# ProPrj_Final_Main_2026-01-12.net
KiCad netlist of a schematic drawn in EasyEDA Pro
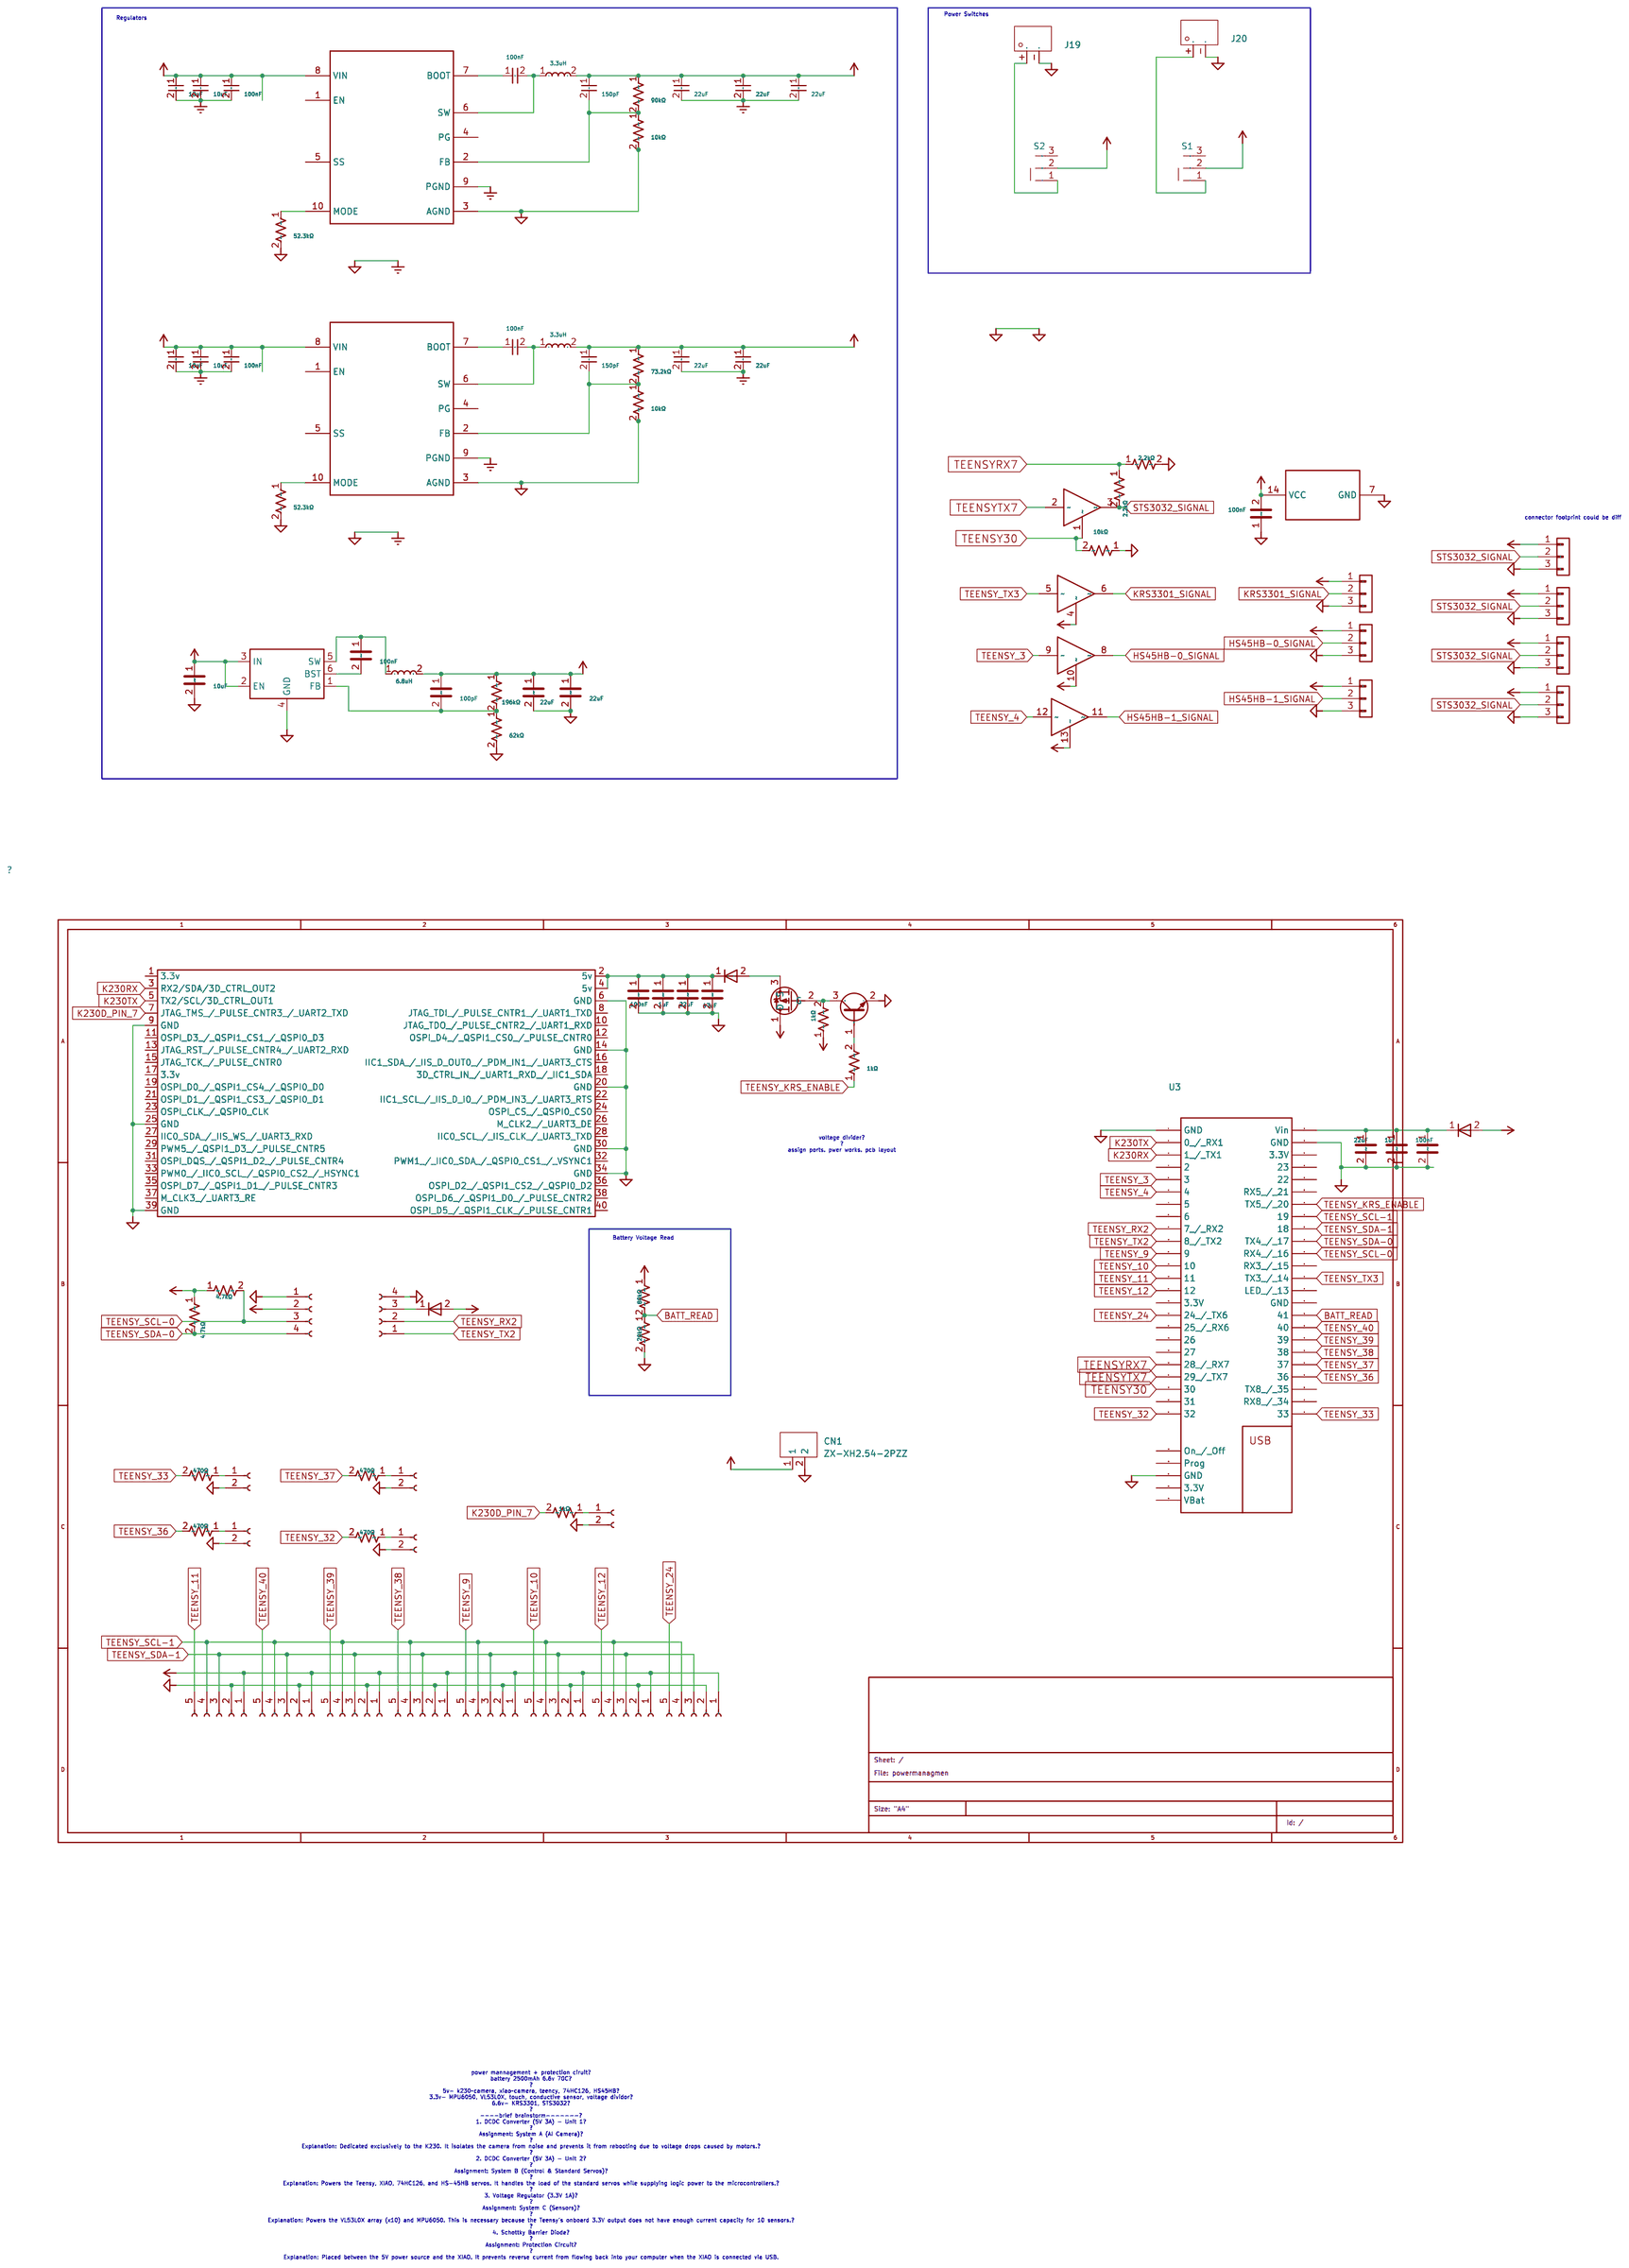
[diagram p0: schematic sheet]

(export (version "E")
  (design (tool "Eeschema 10.0.6"))
  (components
    (comp (ref "C1")
      (value "100nF")
      (description "Capacitance:100nF Tolerance:±10% Tolerance:±10% Voltage Rating:50V Temperature Coefficient:X7R")
      (fields
        (field (name "Manufacturer Part") "TCC0603X7R104K500CT")
        (field (name "Manufacturer") "CCTC(三环)")
      )
      (libsource (lib "easyedapro") (part "Device_C"))
    )
    (comp (ref "C2")
      (value "22uF")
      (description "Capacitance:22uF Tolerance:±20% Tolerance:±20% Voltage Rating:10V Temperature Coefficient:X5R")
      (fields
        (field (name "Manufacturer Part") "CL10A226MP8NUNE")
        (field (name "Manufacturer") "SAMSUNG(三星)")
      )
      (libsource (lib "easyedapro") (part "Device_C"))
    )
    (comp (ref "C3")
      (value "1uF")
      (description "Capacitance:1uF Tolerance:±10% Tolerance:±10% Voltage Rating:50V Temperature Coefficient:X5R")
      (fields
        (field (name "Manufacturer Part") "CL10A105KB8NNNC")
        (field (name "Manufacturer") "SAMSUNG(三星)")
      )
      (libsource (lib "easyedapro") (part "Device_C"))
    )
    (comp (ref "C4")
      (value "100nF")
      (description "Capacitance:100nF Tolerance:±10% Tolerance:±10% Voltage Rating:50V Temperature Coefficient:X7R")
      (fields
        (field (name "Manufacturer Part") "TCC0603X7R104K500CT")
        (field (name "Manufacturer") "CCTC(三环)")
      )
      (libsource (lib "easyedapro") (part "Device_C"))
    )
    (comp (ref "C5")
      (value "10uF")
      (description "Capacitance:10uF Tolerance:±20% Tolerance:±20% Voltage Rating:16V Temperature Coefficient:X5R")
      (fields
        (field (name "Manufacturer Part") "CL10A106MO8NQNC")
        (field (name "Manufacturer") "SAMSUNG(三星)")
      )
      (libsource (lib "easyedapro") (part "Device_C_Small"))
    )
    (comp (ref "C6")
      (value "22uF")
      (description "Capacitance:22uF Tolerance:±20% Tolerance:±20% Voltage Rating:10V Temperature Coefficient:X5R")
      (fields
        (field (name "Manufacturer Part") "CL10A226MP8NUNE")
        (field (name "Manufacturer") "SAMSUNG(三星)")
      )
      (libsource (lib "easyedapro") (part "Device_C_Small"))
    )
    (comp (ref "C7")
      (value "22uF")
      (description "Capacitance:22uF Tolerance:±20% Tolerance:±20% Voltage Rating:10V Temperature Coefficient:X5R")
      (fields
        (field (name "Manufacturer Part") "CL10A226MP8NUNE")
        (field (name "Manufacturer") "SAMSUNG(三星)")
      )
      (libsource (lib "easyedapro") (part "Device_C_Small"))
    )
    (comp (ref "C8")
      (value "22uF")
      (description "Capacitance:22uF Tolerance:±20% Tolerance:±20% Voltage Rating:10V Temperature Coefficient:X5R")
      (fields
        (field (name "Manufacturer Part") "CL10A226MP8NUNE")
        (field (name "Manufacturer") "SAMSUNG(三星)")
      )
      (libsource (lib "easyedapro") (part "Device_C_Small"))
    )
    (comp (ref "C10")
      (value "100pF")
      (description "Capacitance:100pF Tolerance:±5% Tolerance:±5% Voltage Rating:50V Temperature Coefficient:C0G")
      (fields
        (field (name "Manufacturer Part") "CL10C101JB8NNNC")
        (field (name "Manufacturer") "SAMSUNG(三星)")
      )
      (libsource (lib "easyedapro") (part "Device_C"))
    )
    (comp (ref "C12")
      (value "150pF")
      (description "Capacitance:150pF Tolerance:±10% Tolerance:±10% Voltage Rating:50V Temperature Coefficient:X7R")
      (fields (field (name "Manufacturer Part") "0603B151K500NT") (field (name "Manufacturer") "FH(风华)"))
      (libsource (lib "easyedapro") (part "Device_C_Small"))
    )
    (comp (ref "C17")
      (value "100nF")
      (description "Capacitance:100nF Tolerance:±10% Tolerance:±10% Voltage Rating:50V Temperature Coefficient:X7R")
      (fields
        (field (name "Manufacturer Part") "TCC0603X7R104K500CT")
        (field (name "Manufacturer") "CCTC(三环)")
      )
      (libsource (lib "easyedapro") (part "Device_C"))
    )
    (comp (ref "C18")
      (value "1uF")
      (description "Capacitance:1uF Tolerance:±10% Tolerance:±10% Voltage Rating:50V Temperature Coefficient:X5R")
      (fields
        (field (name "Manufacturer Part") "CL10A105KB8NNNC")
        (field (name "Manufacturer") "SAMSUNG(三星)")
      )
      (libsource (lib "easyedapro") (part "Device_C"))
    )
    (comp (ref "C19")
      (value "22uF")
      (description "Capacitance:22uF Tolerance:±20% Tolerance:±20% Voltage Rating:10V Temperature Coefficient:X5R")
      (fields
        (field (name "Manufacturer Part") "CL10A226MP8NUNE")
        (field (name "Manufacturer") "SAMSUNG(三星)")
      )
      (libsource (lib "easyedapro") (part "Device_C"))
    )
    (comp (ref "C20")
      (value "47uF")
      (description "Capacitance:47uF Tolerance:±20% Tolerance:±20% Voltage Rating:6.3V Temperature Coefficient:X5R")
      (fields
        (field (name "Manufacturer Part") "GRM188R60J476ME15D")
        (field (name "Manufacturer") "muRata(村田)")
      )
      (libsource (lib "easyedapro") (part "Device_C"))
    )
    (comp (ref "C21")
      (value "22uF")
      (description "Capacitance:22uF Tolerance:±20% Tolerance:±20% Voltage Rating:10V Temperature Coefficient:X5R")
      (fields
        (field (name "Manufacturer Part") "CL10A226MP8NUNE")
        (field (name "Manufacturer") "SAMSUNG(三星)")
      )
      (libsource (lib "easyedapro") (part "Device_C"))
    )
    (comp (ref "C22")
      (value "10uF")
      (description "Capacitance:10uF Tolerance:±20% Tolerance:±20% Voltage Rating:16V Temperature Coefficient:X5R")
      (fields
        (field (name "Manufacturer Part") "CL10A106MO8NQNC")
        (field (name "Manufacturer") "SAMSUNG(三星)")
      )
      (libsource (lib "easyedapro") (part "Device_C_Small"))
    )
    (comp (ref "C23")
      (value "100nF")
      (description "Capacitance:100nF Tolerance:±10% Tolerance:±10% Voltage Rating:50V Temperature Coefficient:X7R")
      (fields
        (field (name "Manufacturer Part") "TCC0603X7R104K500CT")
        (field (name "Manufacturer") "CCTC(三环)")
      )
      (libsource (lib "easyedapro") (part "Device_C"))
    )
    (comp (ref "C24")
      (value "100nF")
      (description "Capacitance:100nF Tolerance:±10% Tolerance:±10% Voltage Rating:50V Temperature Coefficient:X7R")
      (fields
        (field (name "Manufacturer Part") "TCC0603X7R104K500CT")
        (field (name "Manufacturer") "CCTC(三环)")
      )
      (libsource (lib "easyedapro") (part "Device_C_Small"))
    )
    (comp (ref "C28")
      (value "100nF")
      (description "Capacitance:100nF Tolerance:±10% Tolerance:±10% Voltage Rating:50V Temperature Coefficient:X7R")
      (fields
        (field (name "Manufacturer Part") "TCC0603X7R104K500CT")
        (field (name "Manufacturer") "CCTC(三环)")
      )
      (libsource (lib "easyedapro") (part "Device_C_Small"))
    )
    (comp (ref "C29")
      (value "22uF")
      (description "Capacitance:22uF Tolerance:±20% Tolerance:±20% Voltage Rating:10V Temperature Coefficient:X5R")
      (fields
        (field (name "Manufacturer Part") "CL10A226MP8NUNE")
        (field (name "Manufacturer") "SAMSUNG(三星)")
      )
      (libsource (lib "easyedapro") (part "Device_C"))
    )
    (comp (ref "C31")
      (value "10uF")
      (description "Capacitance:10uF Tolerance:±20% Tolerance:±20% Voltage Rating:16V Temperature Coefficient:X5R")
      (fields
        (field (name "Manufacturer Part") "CL10A106MO8NQNC")
        (field (name "Manufacturer") "SAMSUNG(三星)")
      )
      (libsource (lib "easyedapro") (part "Device_C"))
    )
    (comp (ref "C32")
      (value "100nF")
      (description "Capacitance:100nF Tolerance:±10% Tolerance:±10% Voltage Rating:50V Temperature Coefficient:X7R")
      (fields
        (field (name "Manufacturer Part") "TCC0603X7R104K500CT")
        (field (name "Manufacturer") "CCTC(三环)")
      )
      (libsource (lib "easyedapro") (part "Device_C_Small"))
    )
    (comp (ref "C33")
      (value "100nF")
      (description "Capacitance:100nF Tolerance:±10% Tolerance:±10% Voltage Rating:50V Temperature Coefficient:X7R")
      (fields
        (field (name "Manufacturer Part") "TCC0603X7R104K500CT")
        (field (name "Manufacturer") "CCTC(三环)")
      )
      (libsource (lib "easyedapro") (part "Device_C_Small"))
    )
    (comp (ref "C34")
      (value "10uF")
      (description "Capacitance:10uF Tolerance:±20% Tolerance:±20% Voltage Rating:16V Temperature Coefficient:X5R")
      (fields
        (field (name "Manufacturer Part") "CL10A106MO8NQNC")
        (field (name "Manufacturer") "SAMSUNG(三星)")
      )
      (libsource (lib "easyedapro") (part "Device_C_Small"))
    )
    (comp (ref "C35")
      (value "10uF")
      (description "Capacitance:10uF Tolerance:±20% Tolerance:±20% Voltage Rating:16V Temperature Coefficient:X5R")
      (fields
        (field (name "Manufacturer Part") "CL10A106MO8NQNC")
        (field (name "Manufacturer") "SAMSUNG(三星)")
      )
      (libsource (lib "easyedapro") (part "Device_C_Small"))
    )
    (comp (ref "C36")
      (value "22uF")
      (description "Capacitance:22uF Tolerance:±20% Tolerance:±20% Voltage Rating:10V Temperature Coefficient:X5R")
      (fields
        (field (name "Manufacturer Part") "CL10A226MP8NUNE")
        (field (name "Manufacturer") "SAMSUNG(三星)")
      )
      (libsource (lib "easyedapro") (part "Device_C_Small"))
    )
    (comp (ref "C37")
      (value "22uF")
      (description "Capacitance:22uF Tolerance:±20% Tolerance:±20% Voltage Rating:10V Temperature Coefficient:X5R")
      (fields
        (field (name "Manufacturer Part") "CL10A226MP8NUNE")
        (field (name "Manufacturer") "SAMSUNG(三星)")
      )
      (libsource (lib "easyedapro") (part "Device_C_Small"))
    )
    (comp (ref "C39")
      (value "150pF")
      (description "Capacitance:150pF Tolerance:±10% Tolerance:±10% Voltage Rating:50V Temperature Coefficient:X7R")
      (fields (field (name "Manufacturer Part") "0603B151K500NT") (field (name "Manufacturer") "FH(风华)"))
      (libsource (lib "easyedapro") (part "Device_C_Small"))
    )
    (comp (ref "CN1")
      (value "ZX-XH2.54-2PZZ")
      (footprint "easyedapro:CONN-TH_2P-P2.50_HX25003-2A")
      (fields (field (name "Manufacturer") "Megastar(兆星)"))
      (libsource (lib "easyedapro") (part "ZX-XH2.54-2PZZ"))
    )
    (comp (ref "D1")
      (value "BAT60B")
      (fields (field (name "Manufacturer") "R+O(宏嘉诚)"))
      (libsource (lib "easyedapro") (part "Diode_1N4148WT"))
    )
    (comp (ref "D2")
      (value "BAT60B")
      (fields (field (name "Manufacturer") "R+O(宏嘉诚)"))
      (libsource (lib "easyedapro") (part "Diode_1N4148WT"))
    )
    (comp (ref "D3")
      (value "BAT60B")
      (fields (field (name "Manufacturer") "R+O(宏嘉诚)"))
      (libsource (lib "easyedapro") (part "Diode_1N4148WT"))
    )
    (comp (ref "J1")
      (value "B3B-XH-A(LF)(SN)")
      (fields (field (name "Manufacturer") "JST"))
      (libsource (lib "easyedapro") (part "Connector_Generic_Conn_01x03"))
    )
    (comp (ref "J2")
      (value "PZ254V-11-03P")
      (fields (field (name "Manufacturer") "XFCN(兴飞)"))
      (libsource (lib "easyedapro") (part "Connector_Generic_Conn_01x03"))
    )
    (comp (ref "J3")
      (value "PZ254V-11-03P")
      (fields (field (name "Manufacturer") "XFCN(兴飞)"))
      (libsource (lib "easyedapro") (part "Connector_Generic_Conn_01x03"))
    )
    (comp (ref "J4")
      (value "PZ254V-11-03P")
      (fields (field (name "Manufacturer") "XFCN(兴飞)"))
      (libsource (lib "easyedapro") (part "Connector_Generic_Conn_01x03"))
    )
    (comp (ref "J5")
      (value "B4B-PH-K-S(LF)(SN)")
      (fields (field (name "Manufacturer") "JST"))
      (libsource (lib "easyedapro") (part "Connector_Conn_01x04_Socket"))
    )
    (comp (ref "J6")
      (value "B2B-XH-A(LF)(SN)")
      (fields (field (name "Manufacturer") "JST"))
      (libsource (lib "easyedapro") (part "Connector_Conn_01x02_Socket"))
    )
    (comp (ref "J7")
      (value "B2B-XH-A(LF)(SN)")
      (fields (field (name "Manufacturer") "JST"))
      (libsource (lib "easyedapro") (part "Connector_Conn_01x02_Socket"))
    )
    (comp (ref "J8")
      (value "B2B-XH-A(LF)(SN)")
      (fields (field (name "Manufacturer") "JST"))
      (libsource (lib "easyedapro") (part "Connector_Conn_01x02_Socket"))
    )
    (comp (ref "J9")
      (value "B2B-XH-A(LF)(SN)")
      (fields (field (name "Manufacturer") "JST"))
      (libsource (lib "easyedapro") (part "Connector_Conn_01x02_Socket"))
    )
    (comp (ref "J10")
      (value "B2B-XH-A(LF)(SN)")
      (fields (field (name "Manufacturer") "JST"))
      (libsource (lib "easyedapro") (part "Connector_Conn_01x02_Socket"))
    )
    (comp (ref "J12")
      (value "B3B-XH-A(LF)(SN)")
      (fields (field (name "Manufacturer") "JST"))
      (libsource (lib "easyedapro") (part "Connector_Generic_Conn_01x03"))
    )
    (comp (ref "J13")
      (value "B3B-XH-A(LF)(SN)")
      (fields (field (name "Manufacturer") "JST"))
      (libsource (lib "easyedapro") (part "Connector_Generic_Conn_01x03"))
    )
    (comp (ref "J14")
      (value "B3B-XH-A(LF)(SN)")
      (fields (field (name "Manufacturer") "JST"))
      (libsource (lib "easyedapro") (part "Connector_Generic_Conn_01x03"))
    )
    (comp (ref "J18")
      (value "B5B-PH-K-S(LF)(SN)")
      (fields (field (name "Manufacturer") "JST"))
      (libsource (lib "easyedapro") (part "Connector_Conn_01x05_Socket"))
    )
    (comp (ref "J19")
      (value "XT60-F")
      (footprint "easyedapro:CONN-TH_XT60PB-F")
      (fields (field (name "Manufacturer") "AMASS(艾迈斯)"))
      (libsource (lib "easyedapro") (part "XT60-F"))
    )
    (comp (ref "J20")
      (value "XT60-F")
      (footprint "easyedapro:CONN-TH_XT60PB-F")
      (fields (field (name "Manufacturer") "AMASS(艾迈斯)"))
      (libsource (lib "easyedapro") (part "XT60-F"))
    )
    (comp (ref "J25")
      (value "B5B-PH-K-S(LF)(SN)")
      (fields (field (name "Manufacturer") "JST"))
      (libsource (lib "easyedapro") (part "Connector_Conn_01x05_Socket"))
    )
    (comp (ref "J26")
      (value "B5B-PH-K-S(LF)(SN)")
      (fields (field (name "Manufacturer") "JST"))
      (libsource (lib "easyedapro") (part "Connector_Conn_01x05_Socket"))
    )
    (comp (ref "J27")
      (value "B5B-PH-K-S(LF)(SN)")
      (fields (field (name "Manufacturer") "JST"))
      (libsource (lib "easyedapro") (part "Connector_Conn_01x05_Socket"))
    )
    (comp (ref "J28")
      (value "B5B-PH-K-S(LF)(SN)")
      (fields (field (name "Manufacturer") "JST"))
      (libsource (lib "easyedapro") (part "Connector_Conn_01x05_Socket"))
    )
    (comp (ref "J29")
      (value "B5B-PH-K-S(LF)(SN)")
      (fields (field (name "Manufacturer") "JST"))
      (libsource (lib "easyedapro") (part "Connector_Conn_01x05_Socket"))
    )
    (comp (ref "J31")
      (value "22035045")
      (fields (field (name "Manufacturer") "MOLEX"))
      (libsource (lib "easyedapro") (part "Connector_Conn_01x04_Socket"))
    )
    (comp (ref "J32")
      (value "B5B-PH-K-S(LF)(SN)")
      (fields (field (name "Manufacturer") "JST"))
      (libsource (lib "easyedapro") (part "Connector_Conn_01x05_Socket"))
    )
    (comp (ref "J33")
      (value "B5B-PH-K-S(LF)(SN)")
      (fields (field (name "Manufacturer") "JST"))
      (libsource (lib "easyedapro") (part "Connector_Conn_01x05_Socket"))
    )
    (comp (ref "L1")
      (value "3.3uH")
      (description "Inductance: Tolerance:±20% Tolerance:±20% Current Rating: DC Resistance(DCR):19.9mΩ")
      (fields (field (name "Manufacturer Part") "CYA0650-3.3UH") (field (name "Manufacturer") "SHOU HAN(首韩)"))
      (libsource (lib "easyedapro") (part "Device_L"))
    )
    (comp (ref "L3")
      (value "6.8uH")
      (fields
        (field (name "Manufacturer Part") "MGFL2012F6R8MT-LF")
        (field (name "Manufacturer") "microgate(麦捷科技)")
      )
      (libsource (lib "easyedapro") (part "Device_L"))
    )
    (comp (ref "L4")
      (value "3.3uH")
      (description "Inductance: Tolerance:±20% Tolerance:±20% Current Rating: DC Resistance(DCR):19.9mΩ")
      (fields (field (name "Manufacturer Part") "CYA0650-3.3UH") (field (name "Manufacturer") "SHOU HAN(首韩)"))
      (libsource (lib "easyedapro") (part "Device_L"))
    )
    (comp (ref "Q1")
      (value "AO3401A")
      (fields (field (name "Manufacturer") "UMW(友台半导体)"))
      (libsource (lib "easyedapro") (part "Simulation_SPICE_PMOS"))
    )
    (comp (ref "Q2")
      (value "SS8050(RANGE:200-350)")
      (fields (field (name "Manufacturer") "CJ(江苏长电/长晶)"))
      (libsource (lib "easyedapro") (part "Transistor_BJT_SS8050"))
    )
    (comp (ref "R1")
      (value "10kΩ")
      (fields
        (field (name "Manufacturer Part") "0603WAF1002T5E")
        (field (name "Manufacturer") "UNI-ROYAL(厚声)")
      )
      (libsource (lib "easyedapro") (part "Device_R_US"))
    )
    (comp (ref "R2")
      (value "4.7kΩ")
      (fields (field (name "Manufacturer Part") "FRC0603F4701TS") (field (name "Manufacturer") "FOJAN(富捷)"))
      (libsource (lib "easyedapro") (part "Device_R_US"))
    )
    (comp (ref "R3")
      (value "4.7kΩ")
      (fields (field (name "Manufacturer Part") "FRC0603F4701TS") (field (name "Manufacturer") "FOJAN(富捷)"))
      (libsource (lib "easyedapro") (part "Device_R_US"))
    )
    (comp (ref "R4")
      (value "470Ω")
      (fields
        (field (name "Manufacturer Part") "0603WAF4700T5E")
        (field (name "Manufacturer") "UNI-ROYAL(厚声)")
      )
      (libsource (lib "easyedapro") (part "Device_R_US"))
    )
    (comp (ref "R5")
      (value "470Ω")
      (fields
        (field (name "Manufacturer Part") "0603WAF4700T5E")
        (field (name "Manufacturer") "UNI-ROYAL(厚声)")
      )
      (libsource (lib "easyedapro") (part "Device_R_US"))
    )
    (comp (ref "R6")
      (value "470Ω")
      (fields
        (field (name "Manufacturer Part") "0603WAF4700T5E")
        (field (name "Manufacturer") "UNI-ROYAL(厚声)")
      )
      (libsource (lib "easyedapro") (part "Device_R_US"))
    )
    (comp (ref "R7")
      (value "470Ω")
      (fields
        (field (name "Manufacturer Part") "0603WAF4700T5E")
        (field (name "Manufacturer") "UNI-ROYAL(厚声)")
      )
      (libsource (lib "easyedapro") (part "Device_R_US"))
    )
    (comp (ref "R8")
      (value "1kΩ")
      (fields
        (field (name "Manufacturer Part") "0603WAF1001T5E")
        (field (name "Manufacturer") "UNI-ROYAL(厚声)")
      )
      (libsource (lib "easyedapro") (part "Device_R_US"))
    )
    (comp (ref "R9")
      (value "2.2kΩ")
      (fields
        (field (name "Manufacturer Part") "0603WAF2201T5E")
        (field (name "Manufacturer") "UNI-ROYAL(厚声)")
      )
      (libsource (lib "easyedapro") (part "Device_R_US"))
    )
    (comp (ref "R10")
      (value "2.2kΩ")
      (fields
        (field (name "Manufacturer Part") "0603WAF2201T5E")
        (field (name "Manufacturer") "UNI-ROYAL(厚声)")
      )
      (libsource (lib "easyedapro") (part "Device_R_US"))
    )
    (comp (ref "R11")
      (value "52.3kΩ")
      (fields (field (name "Manufacturer Part") "FRC0603F5232TS") (field (name "Manufacturer") "FOJAN(富捷)"))
      (libsource (lib "easyedapro") (part "Device_R_US"))
    )
    (comp (ref "R12")
      (value "196kΩ")
      (fields (field (name "Manufacturer Part") "FRC0603F1963TS") (field (name "Manufacturer") "FOJAN(富捷)"))
      (libsource (lib "easyedapro") (part "Device_R_US"))
    )
    (comp (ref "R13")
      (value "1kΩ")
      (fields
        (field (name "Manufacturer Part") "0603WAF1001T5E")
        (field (name "Manufacturer") "UNI-ROYAL(厚声)")
      )
      (libsource (lib "easyedapro") (part "Device_R_US"))
    )
    (comp (ref "R14")
      (value "1kΩ")
      (fields
        (field (name "Manufacturer Part") "0603WAF1001T5E")
        (field (name "Manufacturer") "UNI-ROYAL(厚声)")
      )
      (libsource (lib "easyedapro") (part "Device_R_US"))
    )
    (comp (ref "R15")
      (value "62kΩ")
      (fields (field (name "Manufacturer Part") "FRC0603F6202TS") (field (name "Manufacturer") "FOJAN(富捷)"))
      (libsource (lib "easyedapro") (part "Device_R_US"))
    )
    (comp (ref "R20")
      (value "90kΩ")
      (fields (field (name "Manufacturer Part") "RT1206DRE0790KL") (field (name "Manufacturer") "YAGEO(国巨)"))
      (libsource (lib "easyedapro") (part "Device_R_US"))
    )
    (comp (ref "R21")
      (value "10kΩ")
      (fields
        (field (name "Manufacturer Part") "0603WAF1002T5E")
        (field (name "Manufacturer") "UNI-ROYAL(厚声)")
      )
      (libsource (lib "easyedapro") (part "Device_R_US"))
    )
    (comp (ref "R22")
      (value "80kΩ")
      (fields (field (name "Manufacturer Part") "ARG03FTC8002N") (field (name "Manufacturer") "Viking(光颉)"))
      (libsource (lib "easyedapro") (part "Device_R_US"))
    )
    (comp (ref "R23")
      (value "20kΩ")
      (fields (field (name "Manufacturer Part") "FRC0603F2002TS") (field (name "Manufacturer") "FOJAN(富捷)"))
      (libsource (lib "easyedapro") (part "Device_R_US"))
    )
    (comp (ref "R24")
      (value "52.3kΩ")
      (fields (field (name "Manufacturer Part") "FRC0603F5232TS") (field (name "Manufacturer") "FOJAN(富捷)"))
      (libsource (lib "easyedapro") (part "Device_R_US"))
    )
    (comp (ref "R25")
      (value "73.2kΩ")
      (fields (field (name "Manufacturer Part") "FRC0603F7322TS") (field (name "Manufacturer") "FOJAN(富捷)"))
      (libsource (lib "easyedapro") (part "Device_R_US"))
    )
    (comp (ref "R26")
      (value "10kΩ")
      (fields
        (field (name "Manufacturer Part") "0603WAF1002T5E")
        (field (name "Manufacturer") "UNI-ROYAL(厚声)")
      )
      (libsource (lib "easyedapro") (part "Device_R_US"))
    )
    (comp (ref "S1")
      (value "SS-12M11G4")
      (footprint "easyedapro:SW-TH_XKB_SS-12M11XX")
      (fields (field (name "Manufacturer") "XKB Connection(中国星坤)"))
      (libsource (lib "easyedapro") (part "SS-12M11G4"))
    )
    (comp (ref "S2")
      (value "SS-12M11G4")
      (footprint "easyedapro:SW-TH_XKB_SS-12M11XX")
      (fields (field (name "Manufacturer") "XKB Connection(中国星坤)"))
      (libsource (lib "easyedapro") (part "SS-12M11G4"))
    )
    (comp (ref "U1")
      (value "DM74LS126AM")
      (fields (field (name "Manufacturer") "onsemi(安森美)"))
      (libsource (lib "easyedapro") (part "74xx_74LS126"))
    )
    (comp (ref "U2")
      (value "FH-00148")
      (fields (field (name "Manufacturer") "Liansheng(连盛)"))
      (libsource (lib "easyedapro") (part "K230D_K230D-Zero"))
    )
    (comp (ref "U3") (value "TEENSY 4.1") (libsource (lib "easyedapro") (part "TEENSY 4.1")))
    (comp (ref "U4")
      (value "AP63201WU-7")
      (fields (field (name "Manufacturer") "DIODES(美台)"))
      (libsource (lib "easyedapro") (part "Regulator_Switching_AP63201WU"))
    )
    (comp (ref "U5")
      (value "TPS56A37RPAR")
      (fields (field (name "Manufacturer") "TI(德州仪器)"))
      (libsource (lib "easyedapro") (part "2026-01-05_00-17-44_TPS56A37RPAR"))
    )
    (comp (ref "U6")
      (value "TPS56A37RPAR")
      (fields (field (name "Manufacturer") "TI(德州仪器)"))
      (libsource (lib "easyedapro") (part "2026-01-05_00-17-44_TPS56A37RPAR"))
    )
  )
  (nets
    (net (code "1") (name "+3.3V") (class "Default")
      (node (ref "C10") (pin "1") (pinfunction "~_1") (pintype "unspecified"))
      (node (ref "C21") (pin "1") (pinfunction "~_1") (pintype "unspecified"))
      (node (ref "C29") (pin "1") (pinfunction "~_1") (pintype "unspecified"))
      (node (ref "J18") (pin "1") (pinfunction "Pin_1_1") (pintype "unspecified"))
      (node (ref "J25") (pin "1") (pinfunction "Pin_1_1") (pintype "unspecified"))
      (node (ref "J26") (pin "1") (pinfunction "Pin_1_1") (pintype "unspecified"))
      (node (ref "J27") (pin "1") (pinfunction "Pin_1_1") (pintype "unspecified"))
      (node (ref "J28") (pin "1") (pinfunction "Pin_1_1") (pintype "unspecified"))
      (node (ref "J29") (pin "1") (pinfunction "Pin_1_1") (pintype "unspecified"))
      (node (ref "J32") (pin "1") (pinfunction "Pin_1_1") (pintype "unspecified"))
      (node (ref "J33") (pin "1") (pinfunction "Pin_1_1") (pintype "unspecified"))
      (node (ref "J5") (pin "2") (pinfunction "Pin_2_2") (pintype "unspecified"))
      (node (ref "L3") (pin "2") (pinfunction "2_2") (pintype "unspecified"))
      (node (ref "R12") (pin "1") (pinfunction "~_1") (pintype "unspecified"))
      (node (ref "R2") (pin "1") (pinfunction "~_1") (pintype "unspecified"))
      (node (ref "R3") (pin "1") (pinfunction "~_1") (pintype "unspecified"))
    )
    (net (code "2") (name "+5V") (class "Default")
      (node (ref "C1") (pin "2") (pinfunction "~_2") (pintype "unspecified"))
      (node (ref "C36") (pin "1") (pinfunction "~_1") (pintype "unspecified"))
      (node (ref "C37") (pin "1") (pinfunction "~_1") (pintype "unspecified"))
      (node (ref "C39") (pin "1") (pinfunction "~_1") (pintype "unspecified"))
      (node (ref "D1") (pin "2") (pinfunction "A_2") (pintype "unspecified"))
      (node (ref "D3") (pin "2") (pinfunction "A_2") (pintype "unspecified"))
      (node (ref "L4") (pin "2") (pinfunction "2_2") (pintype "unspecified"))
      (node (ref "Q1") (pin "1") (pinfunction "D_1") (pintype "unspecified"))
      (node (ref "R13") (pin "1") (pinfunction "~_1") (pintype "unspecified"))
      (node (ref "R25") (pin "1") (pinfunction "~_1") (pintype "unspecified"))
      (node (ref "U1") (pin "10") (pinfunction "~_10") (pintype "input"))
      (node (ref "U1") (pin "13") (pinfunction "~_13") (pintype "input"))
      (node (ref "U1") (pin "14") (pinfunction "VCC_14") (pintype "unspecified"))
      (node (ref "U1") (pin "4") (pinfunction "~_4") (pintype "input"))
    )
    (net (code "3") (name "+6V") (class "Default")
      (node (ref "C12") (pin "1") (pinfunction "~_1") (pintype "unspecified"))
      (node (ref "C6") (pin "1") (pinfunction "~_1") (pintype "unspecified"))
      (node (ref "C7") (pin "1") (pinfunction "~_1") (pintype "unspecified"))
      (node (ref "C8") (pin "1") (pinfunction "~_1") (pintype "unspecified"))
      (node (ref "J1") (pin "1") (pinfunction "Pin_1_1") (pintype "unspecified"))
      (node (ref "J12") (pin "1") (pinfunction "Pin_1_1") (pintype "unspecified"))
      (node (ref "J13") (pin "1") (pinfunction "Pin_1_1") (pintype "unspecified"))
      (node (ref "J14") (pin "1") (pinfunction "Pin_1_1") (pintype "unspecified"))
      (node (ref "J3") (pin "1") (pinfunction "Pin_1_1") (pintype "unspecified"))
      (node (ref "J4") (pin "1") (pinfunction "Pin_1_1") (pintype "unspecified"))
      (node (ref "L1") (pin "2") (pinfunction "2_2") (pintype "unspecified"))
      (node (ref "R20") (pin "1") (pinfunction "~_1") (pintype "unspecified"))
    )
    (net (code "4") (name "+BATT") (class "Default")
      (node (ref "C22") (pin "1") (pinfunction "~_1") (pintype "unspecified"))
      (node (ref "C24") (pin "1") (pinfunction "~_1") (pintype "unspecified"))
      (node (ref "C31") (pin "1") (pinfunction "~_1") (pintype "unspecified"))
      (node (ref "C33") (pin "1") (pinfunction "~_1") (pintype "unspecified"))
      (node (ref "C34") (pin "1") (pinfunction "~_1") (pintype "unspecified"))
      (node (ref "C35") (pin "1") (pinfunction "~_1") (pintype "unspecified"))
      (node (ref "C5") (pin "1") (pinfunction "~_1") (pintype "unspecified"))
      (node (ref "CN1") (pin "1") (pinfunction "1_1") (pintype "unspecified"))
      (node (ref "J2") (pin "1") (pinfunction "Pin_1_1") (pintype "unspecified"))
      (node (ref "R22") (pin "1") (pinfunction "~_1") (pintype "unspecified"))
      (node (ref "S1") (pin "2") (pinfunction "2_2") (pintype "unspecified"))
      (node (ref "S2") (pin "2") (pinfunction "2_2") (pintype "unspecified"))
      (node (ref "U4") (pin "2") (pinfunction "EN_2") (pintype "input"))
      (node (ref "U4") (pin "3") (pinfunction "IN_3") (pintype "unspecified"))
      (node (ref "U5") (pin "8") (pinfunction "VIN_8") (pintype "unspecified"))
      (node (ref "U6") (pin "8") (pinfunction "VIN_8") (pintype "unspecified"))
    )
    (net (code "5") (name "AGND") (class "Default")
      (node (ref "R24") (pin "2") (pinfunction "~_2") (pintype "unspecified"))
      (node (ref "R26") (pin "2") (pinfunction "~_2") (pintype "unspecified"))
      (node (ref "U6") (pin "3") (pinfunction "AGND_3") (pintype "unspecified"))
    )
    (net (code "6") (name "AGND1") (class "Default")
      (node (ref "R11") (pin "2") (pinfunction "~_2") (pintype "unspecified"))
      (node (ref "R21") (pin "2") (pinfunction "~_2") (pintype "unspecified"))
      (node (ref "U5") (pin "3") (pinfunction "AGND_3") (pintype "unspecified"))
    )
    (net (code "7") (name "BATT_READ") (class "Default")
      (node (ref "R22") (pin "2") (pinfunction "~_2") (pintype "unspecified"))
      (node (ref "R23") (pin "1") (pinfunction "~_1") (pintype "unspecified"))
      (node (ref "U3") (pin "40") (pinfunction "41_40") (pintype "unspecified"))
    )
    (net (code "8") (name "HS45HB-0_SIGNAL") (class "Default")
      (node (ref "J3") (pin "2") (pinfunction "Pin_2_2") (pintype "unspecified"))
      (node (ref "U1") (pin "8") (pinfunction "~_8") (pintype "unspecified"))
    )
    (net (code "9") (name "HS45HB-1_SIGNAL") (class "Default")
      (node (ref "J4") (pin "2") (pinfunction "Pin_2_2") (pintype "unspecified"))
      (node (ref "U1") (pin "11") (pinfunction "~_11") (pintype "unspecified"))
    )
    (net (code "10") (name "K230D_PIN_7") (class "Default")
      (node (ref "R8") (pin "2") (pinfunction "~_2") (pintype "unspecified"))
      (node (ref "U2") (pin "7") (pinfunction "JTAG_TMS_/_PULSE_CNTR3_/_UART2_TXD_7") (pintype "output"))
    )
    (net (code "11") (name "K230RX") (class "Default")
      (node (ref "U2") (pin "3") (pinfunction "RX2/SDA/3D_CTRL_OUT2_3") (pintype "input"))
      (node (ref "U3") (pin "3") (pinfunction "1_/_TX1_3") (pintype "unspecified"))
    )
    (net (code "12") (name "K230TX") (class "Default")
      (node (ref "U2") (pin "5") (pinfunction "TX2/SCL/3D_CTRL_OUT1_5") (pintype "bidirectional"))
      (node (ref "U3") (pin "2") (pinfunction "0_/_RX1_2") (pintype "unspecified"))
    )
    (net (code "13") (name "KRS3301_SIGNAL") (class "Default")
      (node (ref "J2") (pin "2") (pinfunction "Pin_2_2") (pintype "unspecified"))
      (node (ref "U1") (pin "6") (pinfunction "~_6") (pintype "unspecified"))
    )
    (net (code "14") (name "MGND") (class "Default")
      (node (ref "C22") (pin "2") (pinfunction "~_2") (pintype "unspecified"))
      (node (ref "C24") (pin "2") (pinfunction "~_2") (pintype "unspecified"))
      (node (ref "C5") (pin "2") (pinfunction "~_2") (pintype "unspecified"))
      (node (ref "C6") (pin "2") (pinfunction "~_2") (pintype "unspecified"))
      (node (ref "C7") (pin "2") (pinfunction "~_2") (pintype "unspecified"))
      (node (ref "C8") (pin "2") (pinfunction "~_2") (pintype "unspecified"))
      (node (ref "J19") (pin "-") (pinfunction "2_-") (pintype "input"))
      (node (ref "U5") (pin "9") (pinfunction "PGND_9") (pintype "unspecified"))
    )
    (net (code "15") (name "Net-(D1-K)") (class "Default")
      (node (ref "C2") (pin "1") (pinfunction "~_1") (pintype "unspecified"))
      (node (ref "C3") (pin "1") (pinfunction "~_1") (pintype "unspecified"))
      (node (ref "C4") (pin "1") (pinfunction "~_1") (pintype "unspecified"))
      (node (ref "D1") (pin "1") (pinfunction "K_1") (pintype "unspecified"))
      (node (ref "U3") (pin "25") (pinfunction "Vin_25") (pintype "unspecified"))
    )
    (net (code "16") (name "Net-(D2-A)") (class "Default")
      (node (ref "D2") (pin "2") (pinfunction "A_2") (pintype "unspecified"))
      (node (ref "Q1") (pin "3") (pinfunction "S_3") (pintype "unspecified"))
    )
    (net (code "17") (name "Net-(D2-K)") (class "Default")
      (node (ref "C17") (pin "1") (pinfunction "~_1") (pintype "unspecified"))
      (node (ref "C18") (pin "1") (pinfunction "~_1") (pintype "unspecified"))
      (node (ref "C19") (pin "1") (pinfunction "~_1") (pintype "unspecified"))
      (node (ref "C20") (pin "1") (pinfunction "~_1") (pintype "unspecified"))
      (node (ref "D2") (pin "1") (pinfunction "K_1") (pintype "unspecified"))
      (node (ref "U2") (pin "2") (pinfunction "5v_2") (pintype "unspecified"))
      (node (ref "U2") (pin "4") (pinfunction "5v_4") (pintype "bidirectional"))
    )
    (net (code "18") (name "Net-(D3-K)") (class "Default")
      (node (ref "D3") (pin "1") (pinfunction "K_1") (pintype "unspecified"))
      (node (ref "J31") (pin "3") (pinfunction "Pin_3_3") (pintype "unspecified"))
    )
    (net (code "19") (name "Net-(J6-Pin_1)") (class "Default")
      (node (ref "J6") (pin "1") (pinfunction "Pin_1_1") (pintype "unspecified"))
      (node (ref "R4") (pin "1") (pinfunction "~_1") (pintype "unspecified"))
    )
    (net (code "20") (name "Net-(J7-Pin_1)") (class "Default")
      (node (ref "J7") (pin "1") (pinfunction "Pin_1_1") (pintype "unspecified"))
      (node (ref "R5") (pin "1") (pinfunction "~_1") (pintype "unspecified"))
    )
    (net (code "21") (name "Net-(J8-Pin_1)") (class "Default")
      (node (ref "J8") (pin "1") (pinfunction "Pin_1_1") (pintype "unspecified"))
      (node (ref "R6") (pin "1") (pinfunction "~_1") (pintype "unspecified"))
    )
    (net (code "22") (name "Net-(J9-Pin_1)") (class "Default")
      (node (ref "J9") (pin "1") (pinfunction "Pin_1_1") (pintype "unspecified"))
      (node (ref "R7") (pin "1") (pinfunction "~_1") (pintype "unspecified"))
    )
    (net (code "23") (name "Net-(J10-Pin_1)") (class "Default")
      (node (ref "J10") (pin "1") (pinfunction "Pin_1_1") (pintype "unspecified"))
      (node (ref "R8") (pin "1") (pinfunction "~_1") (pintype "unspecified"))
    )
    (net (code "24") (name "Net-(J19-1)") (class "Default")
      (node (ref "J19") (pin "+") (pinfunction "1_+") (pintype "input"))
      (node (ref "S2") (pin "1") (pinfunction "1_1") (pintype "unspecified"))
    )
    (net (code "25") (name "Net-(J20-1)") (class "Default")
      (node (ref "J20") (pin "+") (pinfunction "1_+") (pintype "input"))
      (node (ref "S1") (pin "1") (pinfunction "1_1") (pintype "unspecified"))
    )
    (net (code "26") (name "Net-(Q1-G)") (class "Default")
      (node (ref "Q1") (pin "2") (pinfunction "G_2") (pintype "input"))
      (node (ref "Q2") (pin "3") (pinfunction "C_3") (pintype "unspecified"))
      (node (ref "R13") (pin "2") (pinfunction "~_2") (pintype "unspecified"))
    )
    (net (code "27") (name "Net-(Q2-B)") (class "Default")
      (node (ref "Q2") (pin "1") (pinfunction "B_1") (pintype "input"))
      (node (ref "R14") (pin "2") (pinfunction "~_2") (pintype "unspecified"))
    )
    (net (code "28") (name "Net-(U4-BST)") (class "Default")
      (node (ref "C23") (pin "2") (pinfunction "~_2") (pintype "unspecified"))
      (node (ref "U4") (pin "6") (pinfunction "BST_6") (pintype "unspecified"))
    )
    (net (code "29") (name "Net-(U4-FB)") (class "Default")
      (node (ref "C10") (pin "2") (pinfunction "~_2") (pintype "unspecified"))
      (node (ref "R12") (pin "2") (pinfunction "~_2") (pintype "unspecified"))
      (node (ref "R15") (pin "1") (pinfunction "~_1") (pintype "unspecified"))
      (node (ref "U4") (pin "1") (pinfunction "FB_1") (pintype "input"))
    )
    (net (code "30") (name "Net-(U4-SW)") (class "Default")
      (node (ref "C23") (pin "1") (pinfunction "~_1") (pintype "unspecified"))
      (node (ref "L3") (pin "1") (pinfunction "1_1") (pintype "unspecified"))
      (node (ref "U4") (pin "5") (pinfunction "SW_5") (pintype "output"))
    )
    (net (code "31") (name "Net-(U5-BOOT)") (class "Default")
      (node (ref "C28") (pin "1") (pinfunction "~_1") (pintype "unspecified"))
      (node (ref "U5") (pin "7") (pinfunction "BOOT_7") (pintype "unspecified"))
    )
    (net (code "32") (name "Net-(U5-FB)") (class "Default")
      (node (ref "C12") (pin "2") (pinfunction "~_2") (pintype "unspecified"))
      (node (ref "R20") (pin "2") (pinfunction "~_2") (pintype "unspecified"))
      (node (ref "R21") (pin "1") (pinfunction "~_1") (pintype "unspecified"))
      (node (ref "U5") (pin "2") (pinfunction "FB_2") (pintype "unspecified"))
    )
    (net (code "33") (name "Net-(U5-MODE)") (class "Default")
      (node (ref "R11") (pin "1") (pinfunction "~_1") (pintype "unspecified"))
      (node (ref "U5") (pin "10") (pinfunction "MODE_10") (pintype "unspecified"))
    )
    (net (code "34") (name "Net-(U5-SW)") (class "Default")
      (node (ref "C28") (pin "2") (pinfunction "~_2") (pintype "unspecified"))
      (node (ref "L1") (pin "1") (pinfunction "1_1") (pintype "unspecified"))
      (node (ref "U5") (pin "6") (pinfunction "SW_6") (pintype "unspecified"))
    )
    (net (code "35") (name "Net-(U6-BOOT)") (class "Default")
      (node (ref "C32") (pin "1") (pinfunction "~_1") (pintype "unspecified"))
      (node (ref "U6") (pin "7") (pinfunction "BOOT_7") (pintype "unspecified"))
    )
    (net (code "36") (name "Net-(U6-FB)") (class "Default")
      (node (ref "C39") (pin "2") (pinfunction "~_2") (pintype "unspecified"))
      (node (ref "R25") (pin "2") (pinfunction "~_2") (pintype "unspecified"))
      (node (ref "R26") (pin "1") (pinfunction "~_1") (pintype "unspecified"))
      (node (ref "U6") (pin "2") (pinfunction "FB_2") (pintype "unspecified"))
    )
    (net (code "37") (name "Net-(U6-MODE)") (class "Default")
      (node (ref "R24") (pin "1") (pinfunction "~_1") (pintype "unspecified"))
      (node (ref "U6") (pin "10") (pinfunction "MODE_10") (pintype "unspecified"))
    )
    (net (code "38") (name "Net-(U6-SW)") (class "Default")
      (node (ref "C32") (pin "2") (pinfunction "~_2") (pintype "unspecified"))
      (node (ref "L4") (pin "1") (pinfunction "1_1") (pintype "unspecified"))
      (node (ref "U6") (pin "6") (pinfunction "SW_6") (pintype "unspecified"))
    )
    (net (code "39") (name "POWER_GND") (class "Default")
      (node (ref "C1") (pin "1") (pinfunction "~_1") (pintype "unspecified"))
      (node (ref "C17") (pin "2") (pinfunction "~_2") (pintype "unspecified"))
      (node (ref "C18") (pin "2") (pinfunction "~_2") (pintype "unspecified"))
      (node (ref "C19") (pin "2") (pinfunction "~_2") (pintype "unspecified"))
      (node (ref "C2") (pin "2") (pinfunction "~_2") (pintype "unspecified"))
      (node (ref "C20") (pin "2") (pinfunction "~_2") (pintype "unspecified"))
      (node (ref "C21") (pin "2") (pinfunction "~_2") (pintype "unspecified"))
      (node (ref "C29") (pin "2") (pinfunction "~_2") (pintype "unspecified"))
      (node (ref "C3") (pin "2") (pinfunction "~_2") (pintype "unspecified"))
      (node (ref "C31") (pin "2") (pinfunction "~_2") (pintype "unspecified"))
      (node (ref "C33") (pin "2") (pinfunction "~_2") (pintype "unspecified"))
      (node (ref "C34") (pin "2") (pinfunction "~_2") (pintype "unspecified"))
      (node (ref "C35") (pin "2") (pinfunction "~_2") (pintype "unspecified"))
      (node (ref "C36") (pin "2") (pinfunction "~_2") (pintype "unspecified"))
      (node (ref "C37") (pin "2") (pinfunction "~_2") (pintype "unspecified"))
      (node (ref "C4") (pin "2") (pinfunction "~_2") (pintype "unspecified"))
      (node (ref "CN1") (pin "2") (pinfunction "2_2") (pintype "unspecified"))
      (node (ref "J1") (pin "3") (pinfunction "Pin_3_3") (pintype "unspecified"))
      (node (ref "J10") (pin "2") (pinfunction "Pin_2_2") (pintype "unspecified"))
      (node (ref "J12") (pin "3") (pinfunction "Pin_3_3") (pintype "unspecified"))
      (node (ref "J13") (pin "3") (pinfunction "Pin_3_3") (pintype "unspecified"))
      (node (ref "J14") (pin "3") (pinfunction "Pin_3_3") (pintype "unspecified"))
      (node (ref "J18") (pin "2") (pinfunction "Pin_2_2") (pintype "unspecified"))
      (node (ref "J2") (pin "3") (pinfunction "Pin_3_3") (pintype "unspecified"))
      (node (ref "J20") (pin "-") (pinfunction "2_-") (pintype "input"))
      (node (ref "J25") (pin "2") (pinfunction "Pin_2_2") (pintype "unspecified"))
      (node (ref "J26") (pin "2") (pinfunction "Pin_2_2") (pintype "unspecified"))
      (node (ref "J27") (pin "2") (pinfunction "Pin_2_2") (pintype "unspecified"))
      (node (ref "J28") (pin "2") (pinfunction "Pin_2_2") (pintype "unspecified"))
      (node (ref "J29") (pin "2") (pinfunction "Pin_2_2") (pintype "unspecified"))
      (node (ref "J3") (pin "3") (pinfunction "Pin_3_3") (pintype "unspecified"))
      (node (ref "J31") (pin "4") (pinfunction "Pin_4_4") (pintype "unspecified"))
      (node (ref "J32") (pin "2") (pinfunction "Pin_2_2") (pintype "unspecified"))
      (node (ref "J33") (pin "2") (pinfunction "Pin_2_2") (pintype "unspecified"))
      (node (ref "J4") (pin "3") (pinfunction "Pin_3_3") (pintype "unspecified"))
      (node (ref "J5") (pin "1") (pinfunction "Pin_1_1") (pintype "unspecified"))
      (node (ref "J6") (pin "2") (pinfunction "Pin_2_2") (pintype "unspecified"))
      (node (ref "J7") (pin "2") (pinfunction "Pin_2_2") (pintype "unspecified"))
      (node (ref "J8") (pin "2") (pinfunction "Pin_2_2") (pintype "unspecified"))
      (node (ref "J9") (pin "2") (pinfunction "Pin_2_2") (pintype "unspecified"))
      (node (ref "Q2") (pin "2") (pinfunction "E_2") (pintype "unspecified"))
      (node (ref "R1") (pin "1") (pinfunction "~_1") (pintype "unspecified"))
      (node (ref "R10") (pin "2") (pinfunction "~_2") (pintype "unspecified"))
      (node (ref "R15") (pin "2") (pinfunction "~_2") (pintype "unspecified"))
      (node (ref "R23") (pin "2") (pinfunction "~_2") (pintype "unspecified"))
      (node (ref "U1") (pin "7") (pinfunction "GND_7") (pintype "unspecified"))
      (node (ref "U2") (pin "14") (pinfunction "GND_14") (pintype "bidirectional"))
      (node (ref "U2") (pin "20") (pinfunction "GND_20") (pintype "bidirectional"))
      (node (ref "U2") (pin "25") (pinfunction "GND_25") (pintype "bidirectional"))
      (node (ref "U2") (pin "30") (pinfunction "GND_30") (pintype "bidirectional"))
      (node (ref "U2") (pin "34") (pinfunction "GND_34") (pintype "bidirectional"))
      (node (ref "U2") (pin "39") (pinfunction "GND_39") (pintype "bidirectional"))
      (node (ref "U2") (pin "6") (pinfunction "GND_6") (pintype "bidirectional"))
      (node (ref "U2") (pin "9") (pinfunction "GND_9") (pintype "bidirectional"))
      (node (ref "U3") (pin "1") (pinfunction "GND_1") (pintype "unspecified"))
      (node (ref "U3") (pin "26") (pinfunction "GND_26") (pintype "unspecified"))
      (node (ref "U3") (pin "51") (pinfunction "GND_51") (pintype "unspecified"))
      (node (ref "U4") (pin "4") (pinfunction "GND_4") (pintype "unspecified"))
      (node (ref "U6") (pin "9") (pinfunction "PGND_9") (pintype "unspecified"))
    )
    (net (code "40") (name "STS3032_SIGNAL") (class "Default")
      (node (ref "J1") (pin "2") (pinfunction "Pin_2_2") (pintype "unspecified"))
      (node (ref "J12") (pin "2") (pinfunction "Pin_2_2") (pintype "unspecified"))
      (node (ref "J13") (pin "2") (pinfunction "Pin_2_2") (pintype "unspecified"))
      (node (ref "J14") (pin "2") (pinfunction "Pin_2_2") (pintype "unspecified"))
      (node (ref "R9") (pin "2") (pinfunction "~_2") (pintype "unspecified"))
      (node (ref "U1") (pin "3") (pinfunction "~_3") (pintype "unspecified"))
    )
    (net (code "41") (name "TEENSY30") (class "Default")
      (node (ref "R1") (pin "2") (pinfunction "~_2") (pintype "unspecified"))
      (node (ref "U1") (pin "1") (pinfunction "~_1") (pintype "input"))
      (node (ref "U3") (pin "22") (pinfunction "30_22") (pintype "unspecified"))
    )
    (net (code "42") (name "TEENSYRX7") (class "Default")
      (node (ref "R10") (pin "1") (pinfunction "~_1") (pintype "unspecified"))
      (node (ref "R9") (pin "1") (pinfunction "~_1") (pintype "unspecified"))
      (node (ref "U3") (pin "20") (pinfunction "28_/_RX7_20") (pintype "unspecified"))
    )
    (net (code "43") (name "TEENSYTX7") (class "Default")
      (node (ref "U1") (pin "2") (pinfunction "~_2") (pintype "input"))
      (node (ref "U3") (pin "21") (pinfunction "29_/_TX7_21") (pintype "unspecified"))
    )
    (net (code "44") (name "TEENSY_3") (class "Default")
      (node (ref "U1") (pin "9") (pinfunction "~_9") (pintype "input"))
      (node (ref "U3") (pin "5") (pinfunction "3_5") (pintype "unspecified"))
    )
    (net (code "45") (name "TEENSY_4") (class "Default")
      (node (ref "U1") (pin "12") (pinfunction "~_12") (pintype "input"))
      (node (ref "U3") (pin "6") (pinfunction "4_6") (pintype "unspecified"))
    )
    (net (code "46") (name "TEENSY_9") (class "Default")
      (node (ref "J28") (pin "5") (pinfunction "Pin_5_5") (pintype "unspecified"))
      (node (ref "U3") (pin "11") (pinfunction "9_11") (pintype "unspecified"))
    )
    (net (code "47") (name "TEENSY_10") (class "Default")
      (node (ref "J29") (pin "5") (pinfunction "Pin_5_5") (pintype "unspecified"))
      (node (ref "U3") (pin "12") (pinfunction "10_12") (pintype "unspecified"))
    )
    (net (code "48") (name "TEENSY_11") (class "Default")
      (node (ref "J25") (pin "5") (pinfunction "Pin_5_5") (pintype "unspecified"))
      (node (ref "U3") (pin "13") (pinfunction "11_13") (pintype "unspecified"))
    )
    (net (code "49") (name "TEENSY_12") (class "Default")
      (node (ref "J32") (pin "5") (pinfunction "Pin_5_5") (pintype "unspecified"))
      (node (ref "U3") (pin "14") (pinfunction "12_14") (pintype "unspecified"))
    )
    (net (code "50") (name "TEENSY_24") (class "Default")
      (node (ref "J33") (pin "5") (pinfunction "Pin_5_5") (pintype "unspecified"))
      (node (ref "U3") (pin "16") (pinfunction "24_/_TX6_16") (pintype "unspecified"))
    )
    (net (code "51") (name "TEENSY_32") (class "Default")
      (node (ref "R7") (pin "2") (pinfunction "~_2") (pintype "unspecified"))
      (node (ref "U3") (pin "24") (pinfunction "32_24") (pintype "unspecified"))
    )
    (net (code "52") (name "TEENSY_33") (class "Default")
      (node (ref "R4") (pin "2") (pinfunction "~_2") (pintype "unspecified"))
      (node (ref "U3") (pin "48") (pinfunction "33_48") (pintype "unspecified"))
    )
    (net (code "53") (name "TEENSY_36") (class "Default")
      (node (ref "R5") (pin "2") (pinfunction "~_2") (pintype "unspecified"))
      (node (ref "U3") (pin "45") (pinfunction "36_45") (pintype "unspecified"))
    )
    (net (code "54") (name "TEENSY_37") (class "Default")
      (node (ref "R6") (pin "2") (pinfunction "~_2") (pintype "unspecified"))
      (node (ref "U3") (pin "44") (pinfunction "37_44") (pintype "unspecified"))
    )
    (net (code "55") (name "TEENSY_38") (class "Default")
      (node (ref "J27") (pin "5") (pinfunction "Pin_5_5") (pintype "unspecified"))
      (node (ref "U3") (pin "43") (pinfunction "38_43") (pintype "unspecified"))
    )
    (net (code "56") (name "TEENSY_39") (class "Default")
      (node (ref "J26") (pin "5") (pinfunction "Pin_5_5") (pintype "unspecified"))
      (node (ref "U3") (pin "42") (pinfunction "39_42") (pintype "unspecified"))
    )
    (net (code "57") (name "TEENSY_40") (class "Default")
      (node (ref "J18") (pin "5") (pinfunction "Pin_5_5") (pintype "unspecified"))
      (node (ref "U3") (pin "41") (pinfunction "40_41") (pintype "unspecified"))
    )
    (net (code "58") (name "TEENSY_KRS_ENABLE") (class "Default")
      (node (ref "R14") (pin "1") (pinfunction "~_1") (pintype "unspecified"))
      (node (ref "U3") (pin "31") (pinfunction "TX5_/_20_31") (pintype "unspecified"))
    )
    (net (code "59") (name "TEENSY_RX2") (class "Default")
      (node (ref "J31") (pin "2") (pinfunction "Pin_2_2") (pintype "unspecified"))
      (node (ref "U3") (pin "9") (pinfunction "7_/_RX2_9") (pintype "unspecified"))
    )
    (net (code "60") (name "TEENSY_SCL-0") (class "Default")
      (node (ref "J5") (pin "3") (pinfunction "Pin_3_3") (pintype "unspecified"))
      (node (ref "R3") (pin "2") (pinfunction "~_2") (pintype "unspecified"))
      (node (ref "U3") (pin "35") (pinfunction "RX4_/_16_35") (pintype "unspecified"))
    )
    (net (code "61") (name "TEENSY_SCL-1") (class "Default")
      (node (ref "J18") (pin "4") (pinfunction "Pin_4_4") (pintype "unspecified"))
      (node (ref "J25") (pin "4") (pinfunction "Pin_4_4") (pintype "unspecified"))
      (node (ref "J26") (pin "4") (pinfunction "Pin_4_4") (pintype "unspecified"))
      (node (ref "J27") (pin "4") (pinfunction "Pin_4_4") (pintype "unspecified"))
      (node (ref "J28") (pin "4") (pinfunction "Pin_4_4") (pintype "unspecified"))
      (node (ref "J29") (pin "4") (pinfunction "Pin_4_4") (pintype "unspecified"))
      (node (ref "J32") (pin "4") (pinfunction "Pin_4_4") (pintype "unspecified"))
      (node (ref "J33") (pin "4") (pinfunction "Pin_4_4") (pintype "unspecified"))
      (node (ref "U3") (pin "32") (pinfunction "19_32") (pintype "unspecified"))
    )
    (net (code "62") (name "TEENSY_SDA-0") (class "Default")
      (node (ref "J5") (pin "4") (pinfunction "Pin_4_4") (pintype "unspecified"))
      (node (ref "R2") (pin "2") (pinfunction "~_2") (pintype "unspecified"))
      (node (ref "U3") (pin "34") (pinfunction "TX4_/_17_34") (pintype "unspecified"))
    )
    (net (code "63") (name "TEENSY_SDA-1") (class "Default")
      (node (ref "J18") (pin "3") (pinfunction "Pin_3_3") (pintype "unspecified"))
      (node (ref "J25") (pin "3") (pinfunction "Pin_3_3") (pintype "unspecified"))
      (node (ref "J26") (pin "3") (pinfunction "Pin_3_3") (pintype "unspecified"))
      (node (ref "J27") (pin "3") (pinfunction "Pin_3_3") (pintype "unspecified"))
      (node (ref "J28") (pin "3") (pinfunction "Pin_3_3") (pintype "unspecified"))
      (node (ref "J29") (pin "3") (pinfunction "Pin_3_3") (pintype "unspecified"))
      (node (ref "J32") (pin "3") (pinfunction "Pin_3_3") (pintype "unspecified"))
      (node (ref "J33") (pin "3") (pinfunction "Pin_3_3") (pintype "unspecified"))
      (node (ref "U3") (pin "33") (pinfunction "18_33") (pintype "unspecified"))
    )
    (net (code "64") (name "TEENSY_TX2") (class "Default")
      (node (ref "J31") (pin "1") (pinfunction "Pin_1_1") (pintype "unspecified"))
      (node (ref "U3") (pin "10") (pinfunction "8_/_TX2_10") (pintype "unspecified"))
    )
    (net (code "65") (name "TEENSY_TX3") (class "Default")
      (node (ref "U1") (pin "5") (pinfunction "~_5") (pintype "input"))
      (node (ref "U3") (pin "37") (pinfunction "TX3_/_14_37") (pintype "unspecified"))
    )
    (net (code "66") (name "unconnected-(S1-Pad3)") (class "Default")
      (node (ref "S1") (pin "3") (pinfunction "3_3") (pintype "unspecified"))
    )
    (net (code "67") (name "unconnected-(S2-Pad3)") (class "Default")
      (node (ref "S2") (pin "3") (pinfunction "3_3") (pintype "unspecified"))
    )
    (net (code "68") (name "unconnected-(U2-3.3v-Pad1)") (class "Default")
      (node (ref "U2") (pin "1") (pinfunction "3.3v_1") (pintype "unspecified"))
    )
    (net (code "69") (name "unconnected-(U2-3.3v-Pad17)") (class "Default")
      (node (ref "U2") (pin "17") (pinfunction "3.3v_17") (pintype "bidirectional"))
    )
    (net (code "70") (name "unconnected-(U2-3D_CTRL_IN_{slash}_UART1_RXD_{slash}_IIC1_SDA-Pad18)") (class "Default")
      (node (ref "U2") (pin "18") (pinfunction "3D_CTRL_IN_/_UART1_RXD_/_IIC1_SDA_18") (pintype "bidirectional"))
    )
    (net (code "71") (name "unconnected-(U2-IIC0_SCL_{slash}_IIS_CLK_{slash}_UART3_TXD-Pad28)") (class "Default")
      (node (ref "U2") (pin "28") (pinfunction "IIC0_SCL_/_IIS_CLK_/_UART3_TXD_28") (pintype "bidirectional"))
    )
    (net (code "72") (name "unconnected-(U2-IIC0_SDA_{slash}_IIS_WS_{slash}_UART3_RXD-Pad27)") (class "Default")
      (node (ref "U2") (pin "27") (pinfunction "IIC0_SDA_/_IIS_WS_/_UART3_RXD_27") (pintype "bidirectional"))
    )
    (net (code "73") (name "unconnected-(U2-IIC1_SCL_{slash}_IIS_D_I0_{slash}_PDM_IN3_{slash}_UART3_RTS-Pad22)") (class "Default")
      (node (ref "U2") (pin "22") (pinfunction "IIC1_SCL_/_IIS_D_I0_/_PDM_IN3_/_UART3_RTS_22") (pintype "bidirectional"))
    )
    (net (code "74") (name "unconnected-(U2-IIC1_SDA_{slash}_IIS_D_OUT0_{slash}_PDM_IN1_{slash}_UART3_CTS-Pad16)") (class "Default")
      (node (ref "U2") (pin "16") (pinfunction "IIC1_SDA_/_IIS_D_OUT0_/_PDM_IN1_/_UART3_CTS_16") (pintype "bidirectional"))
    )
    (net (code "75") (name "unconnected-(U2-JTAG_RST_{slash}_PULSE_CNTR4_{slash}_UART2_RXD-Pad13)") (class "Default")
      (node (ref "U2") (pin "13") (pinfunction "JTAG_RST_/_PULSE_CNTR4_/_UART2_RXD_13") (pintype "bidirectional"))
    )
    (net (code "76") (name "unconnected-(U2-JTAG_TCK_{slash}_PULSE_CNTR0-Pad15)") (class "Default")
      (node (ref "U2") (pin "15") (pinfunction "JTAG_TCK_/_PULSE_CNTR0_15") (pintype "bidirectional"))
    )
    (net (code "77") (name "unconnected-(U2-JTAG_TDI_{slash}_PULSE_CNTR1_{slash}_UART1_TXD-Pad8)") (class "Default")
      (node (ref "U2") (pin "8") (pinfunction "JTAG_TDI_/_PULSE_CNTR1_/_UART1_TXD_8") (pintype "bidirectional"))
    )
    (net (code "78") (name "unconnected-(U2-JTAG_TDO_{slash}_PULSE_CNTR2_{slash}_UART1_RXD-Pad10)") (class "Default")
      (node (ref "U2") (pin "10") (pinfunction "JTAG_TDO_/_PULSE_CNTR2_/_UART1_RXD_10") (pintype "bidirectional"))
    )
    (net (code "79") (name "unconnected-(U2-M_CLK2_{slash}_UART3_DE-Pad26)") (class "Default")
      (node (ref "U2") (pin "26") (pinfunction "M_CLK2_/_UART3_DE_26") (pintype "bidirectional"))
    )
    (net (code "80") (name "unconnected-(U2-M_CLK3_{slash}_UART3_RE-Pad37)") (class "Default")
      (node (ref "U2") (pin "37") (pinfunction "M_CLK3_/_UART3_RE_37") (pintype "bidirectional"))
    )
    (net (code "81") (name "unconnected-(U2-OSPI_CLK_{slash}_QSPI0_CLK-Pad23)") (class "Default")
      (node (ref "U2") (pin "23") (pinfunction "OSPI_CLK_/_QSPI0_CLK_23") (pintype "bidirectional"))
    )
    (net (code "82") (name "unconnected-(U2-OSPI_CS_{slash}_QSPI0_CS0-Pad24)") (class "Default")
      (node (ref "U2") (pin "24") (pinfunction "OSPI_CS_/_QSPI0_CS0_24") (pintype "bidirectional"))
    )
    (net (code "83") (name "unconnected-(U2-OSPI_D0_{slash}_QSPI1_CS4_{slash}_QSPI0_D0-Pad19)") (class "Default")
      (node (ref "U2") (pin "19") (pinfunction "OSPI_D0_/_QSPI1_CS4_/_QSPI0_D0_19") (pintype "bidirectional"))
    )
    (net (code "84") (name "unconnected-(U2-OSPI_D1_{slash}_QSPI1_CS3_{slash}_QSPI0_D1-Pad21)") (class "Default")
      (node (ref "U2") (pin "21") (pinfunction "OSPI_D1_/_QSPI1_CS3_/_QSPI0_D1_21") (pintype "bidirectional"))
    )
    (net (code "85") (name "unconnected-(U2-OSPI_D2_{slash}_QSPI1_CS2_{slash}_QSPI0_D2-Pad36)") (class "Default")
      (node (ref "U2") (pin "36") (pinfunction "OSPI_D2_/_QSPI1_CS2_/_QSPI0_D2_36") (pintype "bidirectional"))
    )
    (net (code "86") (name "unconnected-(U2-OSPI_D3_{slash}_QSPI1_CS1_{slash}_QSPI0_D3-Pad11)") (class "Default")
      (node (ref "U2") (pin "11") (pinfunction "OSPI_D3_/_QSPI1_CS1_/_QSPI0_D3_11") (pintype "bidirectional"))
    )
    (net (code "87") (name "unconnected-(U2-OSPI_D4_{slash}_QSPI1_CS0_{slash}_PULSE_CNTR0-Pad12)") (class "Default")
      (node (ref "U2") (pin "12") (pinfunction "OSPI_D4_/_QSPI1_CS0_/_PULSE_CNTR0_12") (pintype "bidirectional"))
    )
    (net (code "88") (name "unconnected-(U2-OSPI_D5_{slash}_QSPI1_CLK_{slash}_PULSE_CNTR1-Pad40)") (class "Default")
      (node (ref "U2") (pin "40") (pinfunction "OSPI_D5_/_QSPI1_CLK_/_PULSE_CNTR1_40") (pintype "bidirectional"))
    )
    (net (code "89") (name "unconnected-(U2-OSPI_D6_{slash}_QSPI1_D0_{slash}_PULSE_CNTR2-Pad38)") (class "Default")
      (node (ref "U2") (pin "38") (pinfunction "OSPI_D6_/_QSPI1_D0_/_PULSE_CNTR2_38") (pintype "bidirectional"))
    )
    (net (code "90") (name "unconnected-(U2-OSPI_D7_{slash}_QSPI1_D1_{slash}_PULSE_CNTR3-Pad35)") (class "Default")
      (node (ref "U2") (pin "35") (pinfunction "OSPI_D7_/_QSPI1_D1_/_PULSE_CNTR3_35") (pintype "bidirectional"))
    )
    (net (code "91") (name "unconnected-(U2-OSPI_DQS_{slash}_QSPI1_D2_{slash}_PULSE_CNTR4-Pad31)") (class "Default")
      (node (ref "U2") (pin "31") (pinfunction "OSPI_DQS_/_QSPI1_D2_/_PULSE_CNTR4_31") (pintype "bidirectional"))
    )
    (net (code "92") (name "unconnected-(U2-PWM0_{slash}_IIC0_SCL_{slash}_QSPI0_CS2_{slash}_HSYNC1-Pad33)") (class "Default")
      (node (ref "U2") (pin "33") (pinfunction "PWM0_/_IIC0_SCL_/_QSPI0_CS2_/_HSYNC1_33") (pintype "bidirectional"))
    )
    (net (code "93") (name "unconnected-(U2-PWM1_{slash}_IIC0_SDA_{slash}_QSPI0_CS1_{slash}_VSYNC1-Pad32)") (class "Default")
      (node (ref "U2") (pin "32") (pinfunction "PWM1_/_IIC0_SDA_/_QSPI0_CS1_/_VSYNC1_32") (pintype "bidirectional"))
    )
    (net (code "94") (name "unconnected-(U2-PWM5_{slash}_QSPI1_D3_{slash}_PULSE_CNTR5-Pad29)") (class "Default")
      (node (ref "U2") (pin "29") (pinfunction "PWM5_/_QSPI1_D3_/_PULSE_CNTR5_29") (pintype "bidirectional"))
    )
    (net (code "95") (name "unconnected-(U3-2-Pad4)") (class "Default")
      (node (ref "U3") (pin "4") (pinfunction "2_4") (pintype "unspecified"))
    )
    (net (code "96") (name "unconnected-(U3-3.3V-Pad15)") (class "Default")
      (node (ref "U3") (pin "15") (pinfunction "3.3V_15") (pintype "unspecified"))
    )
    (net (code "97") (name "unconnected-(U3-3.3V-Pad27)") (class "Default")
      (node (ref "U3") (pin "27") (pinfunction "3.3V_27") (pintype "unspecified"))
    )
    (net (code "98") (name "unconnected-(U3-3.3V-Pad52)") (class "Default")
      (node (ref "U3") (pin "52") (pinfunction "3.3V_52") (pintype "unspecified"))
    )
    (net (code "99") (name "unconnected-(U3-5-Pad7)") (class "Default")
      (node (ref "U3") (pin "7") (pinfunction "5_7") (pintype "unspecified"))
    )
    (net (code "100") (name "unconnected-(U3-6-Pad8)") (class "Default")
      (node (ref "U3") (pin "8") (pinfunction "6_8") (pintype "unspecified"))
    )
    (net (code "101") (name "unconnected-(U3-22-Pad29)") (class "Default")
      (node (ref "U3") (pin "29") (pinfunction "22_29") (pintype "unspecified"))
    )
    (net (code "102") (name "unconnected-(U3-23-Pad28)") (class "Default")
      (node (ref "U3") (pin "28") (pinfunction "23_28") (pintype "unspecified"))
    )
    (net (code "103") (name "unconnected-(U3-25_{slash}_RX6-Pad17)") (class "Default")
      (node (ref "U3") (pin "17") (pinfunction "25_/_RX6_17") (pintype "unspecified"))
    )
    (net (code "104") (name "unconnected-(U3-26-Pad18)") (class "Default")
      (node (ref "U3") (pin "18") (pinfunction "26_18") (pintype "unspecified"))
    )
    (net (code "105") (name "unconnected-(U3-27-Pad19)") (class "Default")
      (node (ref "U3") (pin "19") (pinfunction "27_19") (pintype "unspecified"))
    )
    (net (code "106") (name "unconnected-(U3-31-Pad23)") (class "Default")
      (node (ref "U3") (pin "23") (pinfunction "31_23") (pintype "unspecified"))
    )
    (net (code "107") (name "unconnected-(U3-GND-Pad39)") (class "Default")
      (node (ref "U3") (pin "39") (pinfunction "GND_39") (pintype "unspecified"))
    )
    (net (code "108") (name "unconnected-(U3-LED_{slash}_13-Pad38)") (class "Default")
      (node (ref "U3") (pin "38") (pinfunction "LED_/_13_38") (pintype "unspecified"))
    )
    (net (code "109") (name "unconnected-(U3-On_{slash}_Off-Pad49)") (class "Default")
      (node (ref "U3") (pin "49") (pinfunction "On_/_Off_49") (pintype "unspecified"))
    )
    (net (code "110") (name "unconnected-(U3-Prog-Pad50)") (class "Default")
      (node (ref "U3") (pin "50") (pinfunction "Prog_50") (pintype "unspecified"))
    )
    (net (code "111") (name "unconnected-(U3-RX3_{slash}_15-Pad36)") (class "Default")
      (node (ref "U3") (pin "36") (pinfunction "RX3_/_15_36") (pintype "unspecified"))
    )
    (net (code "112") (name "unconnected-(U3-RX5_{slash}_21-Pad30)") (class "Default")
      (node (ref "U3") (pin "30") (pinfunction "RX5_/_21_30") (pintype "unspecified"))
    )
    (net (code "113") (name "unconnected-(U3-RX8_{slash}_34-Pad47)") (class "Default")
      (node (ref "U3") (pin "47") (pinfunction "RX8_/_34_47") (pintype "unspecified"))
    )
    (net (code "114") (name "unconnected-(U3-TX8_{slash}_35-Pad46)") (class "Default")
      (node (ref "U3") (pin "46") (pinfunction "TX8_/_35_46") (pintype "unspecified"))
    )
    (net (code "115") (name "unconnected-(U3-VBat-Pad53)") (class "Default")
      (node (ref "U3") (pin "53") (pinfunction "VBat_53") (pintype "unspecified"))
    )
    (net (code "116") (name "unconnected-(U5-EN-Pad1)") (class "Default")
      (node (ref "U5") (pin "1") (pinfunction "EN_1") (pintype "input"))
    )
    (net (code "117") (name "unconnected-(U5-PG-Pad4)") (class "Default")
      (node (ref "U5") (pin "4") (pinfunction "PG_4") (pintype "unspecified"))
    )
    (net (code "118") (name "unconnected-(U5-SS-Pad5)") (class "Default")
      (node (ref "U5") (pin "5") (pinfunction "SS_5") (pintype "unspecified"))
    )
    (net (code "119") (name "unconnected-(U6-EN-Pad1)") (class "Default")
      (node (ref "U6") (pin "1") (pinfunction "EN_1") (pintype "input"))
    )
    (net (code "120") (name "unconnected-(U6-PG-Pad4)") (class "Default")
      (node (ref "U6") (pin "4") (pinfunction "PG_4") (pintype "unspecified"))
    )
    (net (code "121") (name "unconnected-(U6-SS-Pad5)") (class "Default")
      (node (ref "U6") (pin "5") (pinfunction "SS_5") (pintype "unspecified"))
    )
  )
)
